# 12VInputProtection.net
KiCad netlist of a schematic drawn in Altium Designer
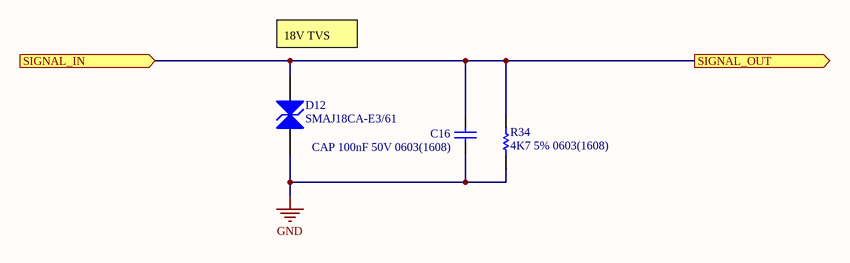
[diagram p0: 12VInputProtection.SchDoc]

(export (version "E")
  (design (tool "Eeschema 10.0.6"))
  (components
    (comp (ref "C16")
      (value "CAP 100nF 50V 0603(1608)")
      (footprint "CAPC0603(1608)100_L")
      (description "CAP 100nF 50V ±5% 0603 (1608 Metric) Thickness 1mm SMD")
      (fields (field (name "TOLERANCE") "Â±5%"))
      (libsource (lib "Altium Content Vault") (part "CAP"))
    )
    (comp (ref "D12")
      (value "SMAJ18CA-E3/61")
      (footprint "VISH-DO-214AC-2_M")
      (fields (field (name "MANUFACTURER") "Vishay Semiconductor"))
      (libsource (lib "Altium Content Vault") (part "VISH-A1A2-2"))
    )
    (comp (ref "R34")
      (value "4K7 5% 0603(1608)")
      (footprint "RESC0603(1608)_N")
      (description "4K7 0.1W 5% 0603 (1608 Metric)  SMD")
      (fields (field (name "TOLERANCE") "5 %") (field (name "POWER") "0.1 W"))
      (libsource (lib "Altium Content Vault") (part "RES"))
    )
  )
  (nets
    (net (code "1") (name "/SIGNAL_IN") (class "Default")
      (node (ref "C16") (pin "1") (pinfunction "1_1") (pintype "passive"))
      (node (ref "D12") (pin "2") (pinfunction "A2_2") (pintype "passive"))
      (node (ref "R34") (pin "2") (pinfunction "2_2") (pintype "passive"))
    )
    (net (code "2") (name "GND") (class "Default")
      (node (ref "C16") (pin "2") (pinfunction "2_2") (pintype "passive"))
      (node (ref "D12") (pin "1") (pinfunction "A1_1") (pintype "passive"))
      (node (ref "R34") (pin "1") (pinfunction "1_1") (pintype "passive"))
    )
  )
)
